# TXn_v1_2.net
KiCad netlist of a schematic drawn in EAGLE
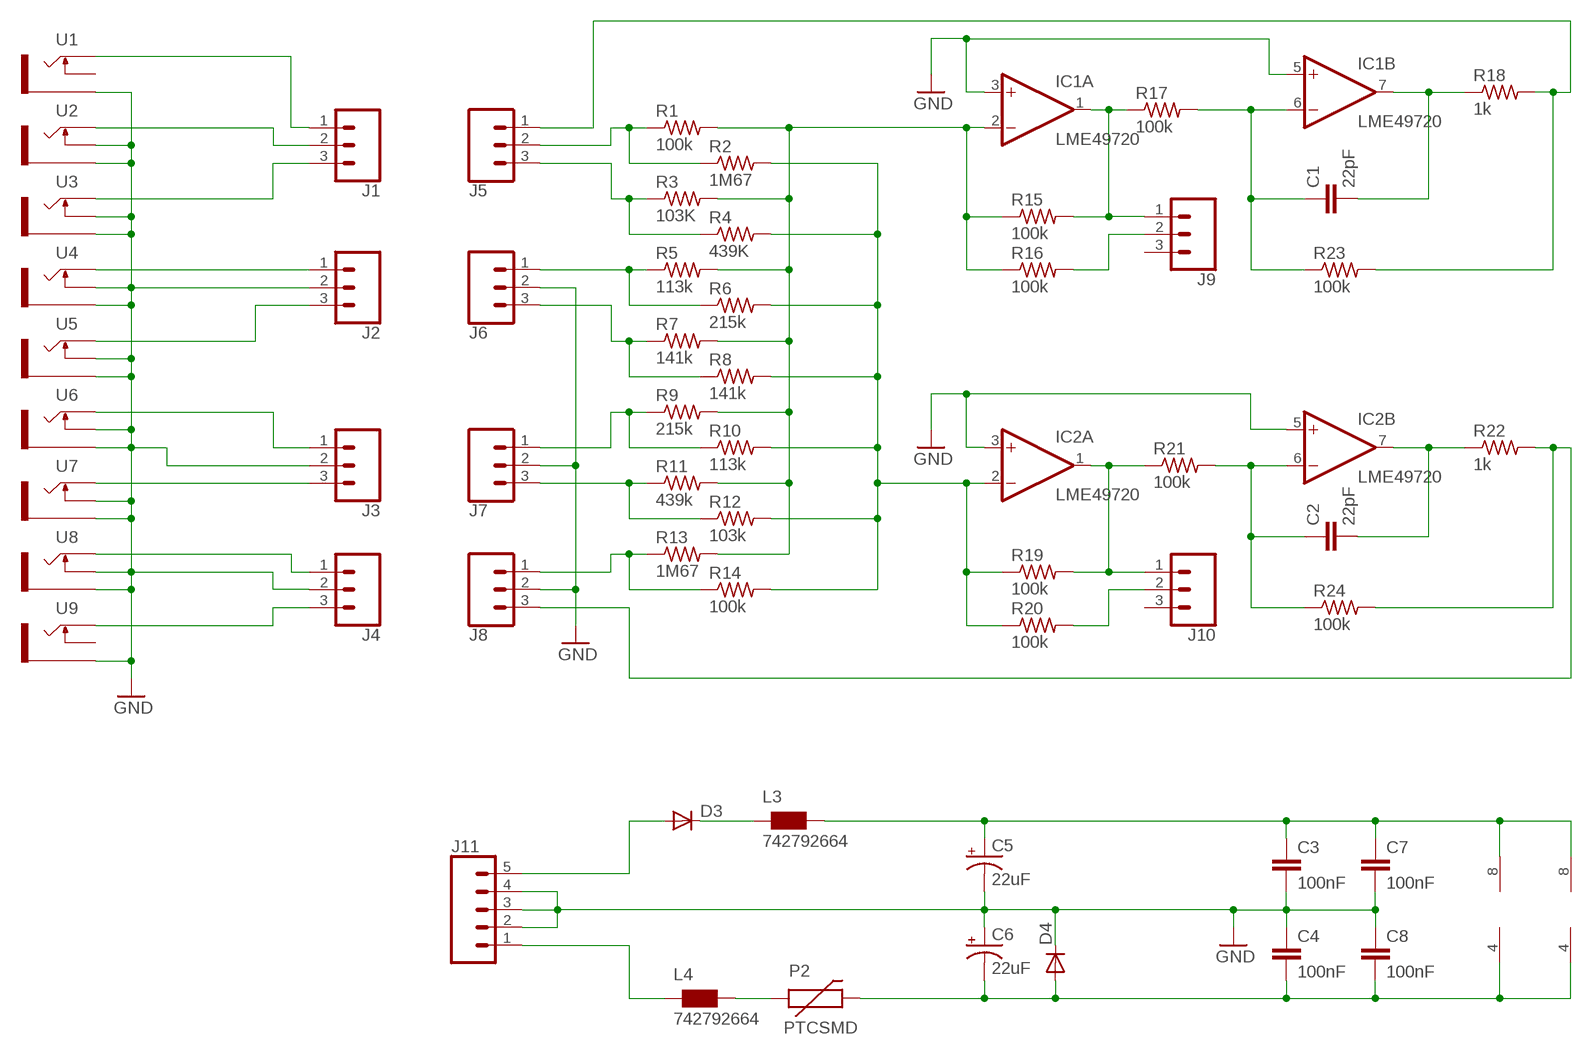
[diagram p0: schematic, sheet 1]

(export (version "E")
  (design (tool "Eeschema 10.0.6"))
  (components
    (comp (ref "C1")
      (value "22pF")
      (footprint "eagle-import:0603-CAP")
      (libsource (lib "eagle-import") (part "CAP0603-CAP"))
    )
    (comp (ref "C2")
      (value "22pF")
      (footprint "eagle-import:0603-CAP")
      (libsource (lib "eagle-import") (part "CAP0603-CAP"))
    )
    (comp (ref "C3")
      (value "100nF")
      (footprint "eagle-import:0603-CAP")
      (libsource (lib "eagle-import") (part "CAP0603-CAP"))
    )
    (comp (ref "C4")
      (value "100nF")
      (footprint "eagle-import:0603-CAP")
      (libsource (lib "eagle-import") (part "CAP0603-CAP"))
    )
    (comp (ref "C5")
      (value "22uF")
      (footprint "eagle-import:PANASONIC_B")
      (libsource (lib "eagle-import") (part "CPOL-USB"))
    )
    (comp (ref "C6")
      (value "22uF")
      (footprint "eagle-import:PANASONIC_B")
      (libsource (lib "eagle-import") (part "CPOL-USB"))
    )
    (comp (ref "C7")
      (value "100nF")
      (footprint "eagle-import:0603-CAP")
      (libsource (lib "eagle-import") (part "CAP0603-CAP"))
    )
    (comp (ref "C8")
      (value "100nF")
      (footprint "eagle-import:0603-CAP")
      (libsource (lib "eagle-import") (part "CAP0603-CAP"))
    )
    (comp (ref "D3")
      (value "DIODE-SOD123")
      (footprint "eagle-import:SOD123")
      (libsource (lib "eagle-import") (part "DIODE-SOD123"))
    )
    (comp (ref "D4")
      (value "DIODE-SOD123")
      (footprint "eagle-import:SOD123")
      (libsource (lib "eagle-import") (part "DIODE-SOD123"))
    )
    (comp (ref "IC1")
      (value "LME49720")
      (footprint "eagle-import:SO08")
      (fields (field (name "SPICEPREFIX") "J"))
      (libsource (lib "eagle-import") (part "TL072D"))
    )
    (comp (ref "IC2")
      (value "LME49720")
      (footprint "eagle-import:SO08")
      (libsource (lib "eagle-import") (part "TL072D"))
    )
    (comp (ref "J1")
      (value "CONN_031X03_NO_SILK")
      (footprint "eagle-import:1X03_NO_SILK")
      (libsource (lib "eagle-import") (part "CONN_031X03_NO_SILK"))
    )
    (comp (ref "J2")
      (value "CONN_031X03_NO_SILK")
      (footprint "eagle-import:1X03_NO_SILK")
      (libsource (lib "eagle-import") (part "CONN_031X03_NO_SILK"))
    )
    (comp (ref "J3")
      (value "CONN_031X03_NO_SILK")
      (footprint "eagle-import:1X03_NO_SILK")
      (libsource (lib "eagle-import") (part "CONN_031X03_NO_SILK"))
    )
    (comp (ref "J4")
      (value "CONN_031X03_NO_SILK")
      (footprint "eagle-import:1X03_NO_SILK")
      (libsource (lib "eagle-import") (part "CONN_031X03_NO_SILK"))
    )
    (comp (ref "J5")
      (value "CONN_031X03_NO_SILK")
      (footprint "eagle-import:1X03_NO_SILK")
      (libsource (lib "eagle-import") (part "CONN_031X03_NO_SILK"))
    )
    (comp (ref "J6")
      (value "CONN_031X03_NO_SILK")
      (footprint "eagle-import:1X03_NO_SILK")
      (libsource (lib "eagle-import") (part "CONN_031X03_NO_SILK"))
    )
    (comp (ref "J7")
      (value "CONN_031X03_NO_SILK")
      (footprint "eagle-import:1X03_NO_SILK")
      (libsource (lib "eagle-import") (part "CONN_031X03_NO_SILK"))
    )
    (comp (ref "J8")
      (value "CONN_031X03_NO_SILK")
      (footprint "eagle-import:1X03_NO_SILK")
      (libsource (lib "eagle-import") (part "CONN_031X03_NO_SILK"))
    )
    (comp (ref "J9")
      (value "CONN_031X03_NO_SILK")
      (footprint "eagle-import:1X03_NO_SILK")
      (libsource (lib "eagle-import") (part "CONN_031X03_NO_SILK"))
    )
    (comp (ref "J10")
      (value "CONN_031X03_NO_SILK")
      (footprint "eagle-import:1X03_NO_SILK")
      (libsource (lib "eagle-import") (part "CONN_031X03_NO_SILK"))
    )
    (comp (ref "J11")
      (value "CONN_05NO_SILK")
      (footprint "eagle-import:1X05_NO_SILK")
      (libsource (lib "eagle-import") (part "CONN_05NO_SILK"))
    )
    (comp (ref "L3")
      (value "742792664")
      (footprint "eagle-import:0603")
      (libsource (lib "eagle-import") (part "WE-CBF_0603"))
    )
    (comp (ref "L4")
      (value "742792664")
      (footprint "eagle-import:0603")
      (libsource (lib "eagle-import") (part "WE-CBF_0603"))
    )
    (comp (ref "P2")
      (value "PTCSMD")
      (footprint "eagle-import:PTC-1206")
      (libsource (lib "eagle-import") (part "PTCSMD"))
    )
    (comp (ref "R1")
      (value "100k")
      (footprint "eagle-import:R0603")
      (libsource (lib "eagle-import") (part "R-US_R0603"))
    )
    (comp (ref "R2")
      (value "1M67")
      (footprint "eagle-import:R0603")
      (libsource (lib "eagle-import") (part "R-US_R0603"))
    )
    (comp (ref "R3")
      (value "103K")
      (footprint "eagle-import:R0603")
      (libsource (lib "eagle-import") (part "R-US_R0603"))
    )
    (comp (ref "R4")
      (value "439K")
      (footprint "eagle-import:R0603")
      (libsource (lib "eagle-import") (part "R-US_R0603"))
    )
    (comp (ref "R5")
      (value "113k")
      (footprint "eagle-import:R0603")
      (libsource (lib "eagle-import") (part "R-US_R0603"))
    )
    (comp (ref "R6")
      (value "215k")
      (footprint "eagle-import:R0603")
      (libsource (lib "eagle-import") (part "R-US_R0603"))
    )
    (comp (ref "R7")
      (value "141k")
      (footprint "eagle-import:R0603")
      (libsource (lib "eagle-import") (part "R-US_R0603"))
    )
    (comp (ref "R8")
      (value "141k")
      (footprint "eagle-import:R0603")
      (libsource (lib "eagle-import") (part "R-US_R0603"))
    )
    (comp (ref "R9")
      (value "215k")
      (footprint "eagle-import:R0603")
      (libsource (lib "eagle-import") (part "R-US_R0603"))
    )
    (comp (ref "R10")
      (value "113k")
      (footprint "eagle-import:R0603")
      (libsource (lib "eagle-import") (part "R-US_R0603"))
    )
    (comp (ref "R11")
      (value "439k")
      (footprint "eagle-import:R0603")
      (libsource (lib "eagle-import") (part "R-US_R0603"))
    )
    (comp (ref "R12")
      (value "103k")
      (footprint "eagle-import:R0603")
      (libsource (lib "eagle-import") (part "R-US_R0603"))
    )
    (comp (ref "R13")
      (value "1M67")
      (footprint "eagle-import:R0603")
      (libsource (lib "eagle-import") (part "R-US_R0603"))
    )
    (comp (ref "R14")
      (value "100k")
      (footprint "eagle-import:R0603")
      (libsource (lib "eagle-import") (part "R-US_R0603"))
    )
    (comp (ref "R15")
      (value "100k")
      (footprint "eagle-import:R0603")
      (libsource (lib "eagle-import") (part "R-US_R0603"))
    )
    (comp (ref "R16")
      (value "100k")
      (footprint "eagle-import:R0603")
      (libsource (lib "eagle-import") (part "R-US_R0603"))
    )
    (comp (ref "R17")
      (value "100k")
      (footprint "eagle-import:R0603")
      (libsource (lib "eagle-import") (part "R-US_R0603"))
    )
    (comp (ref "R18")
      (value "1k")
      (footprint "eagle-import:R0603")
      (libsource (lib "eagle-import") (part "R-US_R0603"))
    )
    (comp (ref "R19")
      (value "100k")
      (footprint "eagle-import:R0603")
      (libsource (lib "eagle-import") (part "R-US_R0603"))
    )
    (comp (ref "R20")
      (value "100k")
      (footprint "eagle-import:R0603")
      (libsource (lib "eagle-import") (part "R-US_R0603"))
    )
    (comp (ref "R21")
      (value "100k")
      (footprint "eagle-import:R0603")
      (libsource (lib "eagle-import") (part "R-US_R0603"))
    )
    (comp (ref "R22")
      (value "1k")
      (footprint "eagle-import:R0603")
      (libsource (lib "eagle-import") (part "R-US_R0603"))
    )
    (comp (ref "R23")
      (value "100k")
      (footprint "eagle-import:R0603")
      (libsource (lib "eagle-import") (part "R-US_R0603"))
    )
    (comp (ref "R24")
      (value "100k")
      (footprint "eagle-import:R0603")
      (libsource (lib "eagle-import") (part "R-US_R0603"))
    )
    (comp (ref "U1")
      (value "THONKICONNLEFT")
      (footprint "eagle-import:WQP-PJ301M-12_JACK_L")
      (libsource (lib "eagle-import") (part "THONKICONNLEFT"))
    )
    (comp (ref "U2")
      (value "THONKICONNLEFT")
      (footprint "eagle-import:WQP-PJ301M-12_JACK_L")
      (libsource (lib "eagle-import") (part "THONKICONNLEFT"))
    )
    (comp (ref "U3")
      (value "THONKICONNLEFT")
      (footprint "eagle-import:WQP-PJ301M-12_JACK_L")
      (libsource (lib "eagle-import") (part "THONKICONNLEFT"))
    )
    (comp (ref "U4")
      (value "THONKICONNLEFT")
      (footprint "eagle-import:WQP-PJ301M-12_JACK_L")
      (libsource (lib "eagle-import") (part "THONKICONNLEFT"))
    )
    (comp (ref "U5")
      (value "THONKICONNLEFT")
      (footprint "eagle-import:WQP-PJ301M-12_JACK_L")
      (libsource (lib "eagle-import") (part "THONKICONNLEFT"))
    )
    (comp (ref "U6")
      (value "THONKICONNLEFT")
      (footprint "eagle-import:WQP-PJ301M-12_JACK_L")
      (libsource (lib "eagle-import") (part "THONKICONNLEFT"))
    )
    (comp (ref "U7")
      (value "THONKICONNLEFT")
      (footprint "eagle-import:WQP-PJ301M-12_JACK_L")
      (libsource (lib "eagle-import") (part "THONKICONNLEFT"))
    )
    (comp (ref "U8")
      (value "THONKICONNLEFT")
      (footprint "eagle-import:WQP-PJ301M-12_JACK_L")
      (libsource (lib "eagle-import") (part "THONKICONNLEFT"))
    )
    (comp (ref "U9")
      (value "THONKICONNLEFT")
      (footprint "eagle-import:WQP-PJ301M-12_JACK_L")
      (libsource (lib "eagle-import") (part "THONKICONNLEFT"))
    )
  )
  (nets
    (net (code "1") (name "GND") (class "Default")
      (node (ref "C3") (pin "2") (pinfunction "2_2") (pintype "passive"))
      (node (ref "C4") (pin "1") (pinfunction "1_1") (pintype "passive"))
      (node (ref "C5") (pin "-") (pinfunction "-_-") (pintype "passive"))
      (node (ref "C6") (pin "+") (pinfunction "+_+") (pintype "passive"))
      (node (ref "C7") (pin "2") (pinfunction "2_2") (pintype "passive"))
      (node (ref "C8") (pin "1") (pinfunction "1_1") (pintype "passive"))
      (node (ref "D4") (pin "C") (pinfunction "C_C") (pintype "passive"))
      (node (ref "IC1") (pin "3") (pinfunction "+IN_3") (pintype "input"))
      (node (ref "IC1") (pin "5") (pinfunction "+IN_5") (pintype "input"))
      (node (ref "IC2") (pin "3") (pinfunction "+IN_3") (pintype "input"))
      (node (ref "IC2") (pin "5") (pinfunction "+IN_5") (pintype "input"))
      (node (ref "J11") (pin "2") (pinfunction "2_2") (pintype "passive"))
      (node (ref "J11") (pin "3") (pinfunction "3_3") (pintype "passive"))
      (node (ref "J11") (pin "4") (pinfunction "4_4") (pintype "passive"))
      (node (ref "J2") (pin "2") (pinfunction "2_2") (pintype "passive"))
      (node (ref "J3") (pin "2") (pinfunction "2_2") (pintype "passive"))
      (node (ref "J4") (pin "2") (pinfunction "2_2") (pintype "passive"))
      (node (ref "J6") (pin "2") (pinfunction "2_2") (pintype "passive"))
      (node (ref "J7") (pin "2") (pinfunction "2_2") (pintype "passive"))
      (node (ref "J8") (pin "2") (pinfunction "2_2") (pintype "passive"))
      (node (ref "U1") (pin "P$3_SLEEVE") (pinfunction "SLEEVE_P$3_SLEEVE") (pintype "passive"))
      (node (ref "U2") (pin "P$2_SWITCH") (pinfunction "SWITCH_P$2_SWITCH") (pintype "passive"))
      (node (ref "U2") (pin "P$3_SLEEVE") (pinfunction "SLEEVE_P$3_SLEEVE") (pintype "passive"))
      (node (ref "U3") (pin "P$2_SWITCH") (pinfunction "SWITCH_P$2_SWITCH") (pintype "passive"))
      (node (ref "U3") (pin "P$3_SLEEVE") (pinfunction "SLEEVE_P$3_SLEEVE") (pintype "passive"))
      (node (ref "U4") (pin "P$2_SWITCH") (pinfunction "SWITCH_P$2_SWITCH") (pintype "passive"))
      (node (ref "U4") (pin "P$3_SLEEVE") (pinfunction "SLEEVE_P$3_SLEEVE") (pintype "passive"))
      (node (ref "U5") (pin "P$2_SWITCH") (pinfunction "SWITCH_P$2_SWITCH") (pintype "passive"))
      (node (ref "U5") (pin "P$3_SLEEVE") (pinfunction "SLEEVE_P$3_SLEEVE") (pintype "passive"))
      (node (ref "U6") (pin "P$2_SWITCH") (pinfunction "SWITCH_P$2_SWITCH") (pintype "passive"))
      (node (ref "U6") (pin "P$3_SLEEVE") (pinfunction "SLEEVE_P$3_SLEEVE") (pintype "passive"))
      (node (ref "U7") (pin "P$2_SWITCH") (pinfunction "SWITCH_P$2_SWITCH") (pintype "passive"))
      (node (ref "U7") (pin "P$3_SLEEVE") (pinfunction "SLEEVE_P$3_SLEEVE") (pintype "passive"))
      (node (ref "U8") (pin "P$2_SWITCH") (pinfunction "SWITCH_P$2_SWITCH") (pintype "passive"))
      (node (ref "U8") (pin "P$3_SLEEVE") (pinfunction "SLEEVE_P$3_SLEEVE") (pintype "passive"))
      (node (ref "U9") (pin "P$3_SLEEVE") (pinfunction "SLEEVE_P$3_SLEEVE") (pintype "passive"))
    )
    (net (code "2") (name "Net-(D3-PadA)") (class "Default")
      (node (ref "D3") (pin "A") (pinfunction "A_A") (pintype "passive"))
      (node (ref "J11") (pin "5") (pinfunction "5_5") (pintype "passive"))
    )
    (net (code "3") (name "Net-(D3-PadC)") (class "Default")
      (node (ref "D3") (pin "C") (pinfunction "C_C") (pintype "passive"))
      (node (ref "L3") (pin "1") (pinfunction "1_1") (pintype "passive"))
    )
    (net (code "4") (name "Net-(IC1A--IN)") (class "Default")
      (node (ref "IC1") (pin "2") (pinfunction "-IN_2") (pintype "input"))
      (node (ref "R1") (pin "2") (pinfunction "2_2") (pintype "passive"))
      (node (ref "R11") (pin "2") (pinfunction "2_2") (pintype "passive"))
      (node (ref "R13") (pin "2") (pinfunction "2_2") (pintype "passive"))
      (node (ref "R15") (pin "1") (pinfunction "1_1") (pintype "passive"))
      (node (ref "R16") (pin "1") (pinfunction "1_1") (pintype "passive"))
      (node (ref "R3") (pin "2") (pinfunction "2_2") (pintype "passive"))
      (node (ref "R5") (pin "2") (pinfunction "2_2") (pintype "passive"))
      (node (ref "R7") (pin "2") (pinfunction "2_2") (pintype "passive"))
      (node (ref "R9") (pin "2") (pinfunction "2_2") (pintype "passive"))
    )
    (net (code "5") (name "Net-(IC1A-OUT)") (class "Default")
      (node (ref "IC1") (pin "1") (pinfunction "OUT_1") (pintype "output"))
      (node (ref "J9") (pin "1") (pinfunction "1_1") (pintype "passive"))
      (node (ref "R15") (pin "2") (pinfunction "2_2") (pintype "passive"))
      (node (ref "R17") (pin "1") (pinfunction "1_1") (pintype "passive"))
    )
    (net (code "6") (name "Net-(IC1B--IN)") (class "Default")
      (node (ref "C1") (pin "1") (pinfunction "1_1") (pintype "passive"))
      (node (ref "IC1") (pin "6") (pinfunction "-IN_6") (pintype "input"))
      (node (ref "R17") (pin "2") (pinfunction "2_2") (pintype "passive"))
      (node (ref "R23") (pin "1") (pinfunction "1_1") (pintype "passive"))
    )
    (net (code "7") (name "Net-(IC1B-OUT)") (class "Default")
      (node (ref "C1") (pin "2") (pinfunction "2_2") (pintype "passive"))
      (node (ref "IC1") (pin "7") (pinfunction "OUT_7") (pintype "output"))
      (node (ref "R18") (pin "1") (pinfunction "1_1") (pintype "passive"))
    )
    (net (code "8") (name "Net-(IC1C-V+)") (class "Default")
      (node (ref "C3") (pin "1") (pinfunction "1_1") (pintype "passive"))
      (node (ref "C5") (pin "+") (pinfunction "+_+") (pintype "passive"))
      (node (ref "C7") (pin "1") (pinfunction "1_1") (pintype "passive"))
      (node (ref "IC1") (pin "8") (pinfunction "V+_8") (pintype "power_in"))
      (node (ref "IC2") (pin "8") (pinfunction "V+_8") (pintype "power_in"))
      (node (ref "L3") (pin "2") (pinfunction "2_2") (pintype "passive"))
    )
    (net (code "9") (name "Net-(IC1C-V-)") (class "Default")
      (node (ref "C4") (pin "2") (pinfunction "2_2") (pintype "passive"))
      (node (ref "C6") (pin "-") (pinfunction "-_-") (pintype "passive"))
      (node (ref "C8") (pin "2") (pinfunction "2_2") (pintype "passive"))
      (node (ref "D4") (pin "A") (pinfunction "A_A") (pintype "passive"))
      (node (ref "IC1") (pin "4") (pinfunction "V-_4") (pintype "power_in"))
      (node (ref "IC2") (pin "4") (pinfunction "V-_4") (pintype "power_in"))
      (node (ref "P2") (pin "2") (pinfunction "2_2") (pintype "bidirectional"))
    )
    (net (code "10") (name "Net-(IC2A--IN)") (class "Default")
      (node (ref "IC2") (pin "2") (pinfunction "-IN_2") (pintype "input"))
      (node (ref "R10") (pin "2") (pinfunction "2_2") (pintype "passive"))
      (node (ref "R12") (pin "2") (pinfunction "2_2") (pintype "passive"))
      (node (ref "R14") (pin "2") (pinfunction "2_2") (pintype "passive"))
      (node (ref "R19") (pin "1") (pinfunction "1_1") (pintype "passive"))
      (node (ref "R2") (pin "2") (pinfunction "2_2") (pintype "passive"))
      (node (ref "R20") (pin "1") (pinfunction "1_1") (pintype "passive"))
      (node (ref "R4") (pin "2") (pinfunction "2_2") (pintype "passive"))
      (node (ref "R6") (pin "2") (pinfunction "2_2") (pintype "passive"))
      (node (ref "R8") (pin "2") (pinfunction "2_2") (pintype "passive"))
    )
    (net (code "11") (name "Net-(IC2A-OUT)") (class "Default")
      (node (ref "IC2") (pin "1") (pinfunction "OUT_1") (pintype "output"))
      (node (ref "J10") (pin "1") (pinfunction "1_1") (pintype "passive"))
      (node (ref "R19") (pin "2") (pinfunction "2_2") (pintype "passive"))
      (node (ref "R21") (pin "1") (pinfunction "1_1") (pintype "passive"))
    )
    (net (code "12") (name "Net-(IC2B--IN)") (class "Default")
      (node (ref "C2") (pin "1") (pinfunction "1_1") (pintype "passive"))
      (node (ref "IC2") (pin "6") (pinfunction "-IN_6") (pintype "input"))
      (node (ref "R21") (pin "2") (pinfunction "2_2") (pintype "passive"))
      (node (ref "R24") (pin "1") (pinfunction "1_1") (pintype "passive"))
    )
    (net (code "13") (name "Net-(IC2B-OUT)") (class "Default")
      (node (ref "C2") (pin "2") (pinfunction "2_2") (pintype "passive"))
      (node (ref "IC2") (pin "7") (pinfunction "OUT_7") (pintype "output"))
      (node (ref "R22") (pin "1") (pinfunction "1_1") (pintype "passive"))
    )
    (net (code "14") (name "Net-(J5-Pad1)") (class "Default")
      (node (ref "J5") (pin "1") (pinfunction "1_1") (pintype "passive"))
      (node (ref "R18") (pin "2") (pinfunction "2_2") (pintype "passive"))
      (node (ref "R23") (pin "2") (pinfunction "2_2") (pintype "passive"))
    )
    (net (code "15") (name "Net-(J5-Pad2)") (class "Default")
      (node (ref "J5") (pin "2") (pinfunction "2_2") (pintype "passive"))
      (node (ref "R1") (pin "1") (pinfunction "1_1") (pintype "passive"))
      (node (ref "R2") (pin "1") (pinfunction "1_1") (pintype "passive"))
    )
    (net (code "16") (name "Net-(J5-Pad3)") (class "Default")
      (node (ref "J5") (pin "3") (pinfunction "3_3") (pintype "passive"))
      (node (ref "R3") (pin "1") (pinfunction "1_1") (pintype "passive"))
      (node (ref "R4") (pin "1") (pinfunction "1_1") (pintype "passive"))
    )
    (net (code "17") (name "Net-(J6-Pad1)") (class "Default")
      (node (ref "J6") (pin "1") (pinfunction "1_1") (pintype "passive"))
      (node (ref "R5") (pin "1") (pinfunction "1_1") (pintype "passive"))
      (node (ref "R6") (pin "1") (pinfunction "1_1") (pintype "passive"))
    )
    (net (code "18") (name "Net-(J6-Pad3)") (class "Default")
      (node (ref "J6") (pin "3") (pinfunction "3_3") (pintype "passive"))
      (node (ref "R7") (pin "1") (pinfunction "1_1") (pintype "passive"))
      (node (ref "R8") (pin "1") (pinfunction "1_1") (pintype "passive"))
    )
    (net (code "19") (name "Net-(J7-Pad1)") (class "Default")
      (node (ref "J7") (pin "1") (pinfunction "1_1") (pintype "passive"))
      (node (ref "R10") (pin "1") (pinfunction "1_1") (pintype "passive"))
      (node (ref "R9") (pin "1") (pinfunction "1_1") (pintype "passive"))
    )
    (net (code "20") (name "Net-(J7-Pad3)") (class "Default")
      (node (ref "J7") (pin "3") (pinfunction "3_3") (pintype "passive"))
      (node (ref "R11") (pin "1") (pinfunction "1_1") (pintype "passive"))
      (node (ref "R12") (pin "1") (pinfunction "1_1") (pintype "passive"))
    )
    (net (code "21") (name "Net-(J8-Pad1)") (class "Default")
      (node (ref "J8") (pin "1") (pinfunction "1_1") (pintype "passive"))
      (node (ref "R13") (pin "1") (pinfunction "1_1") (pintype "passive"))
      (node (ref "R14") (pin "1") (pinfunction "1_1") (pintype "passive"))
    )
    (net (code "22") (name "Net-(J8-Pad3)") (class "Default")
      (node (ref "J8") (pin "3") (pinfunction "3_3") (pintype "passive"))
      (node (ref "R22") (pin "2") (pinfunction "2_2") (pintype "passive"))
      (node (ref "R24") (pin "2") (pinfunction "2_2") (pintype "passive"))
    )
    (net (code "23") (name "Net-(J9-Pad2)") (class "Default")
      (node (ref "J9") (pin "2") (pinfunction "2_2") (pintype "passive"))
      (node (ref "R16") (pin "2") (pinfunction "2_2") (pintype "passive"))
    )
    (net (code "24") (name "Net-(J10-Pad2)") (class "Default")
      (node (ref "J10") (pin "2") (pinfunction "2_2") (pintype "passive"))
      (node (ref "R20") (pin "2") (pinfunction "2_2") (pintype "passive"))
    )
    (net (code "25") (name "Net-(J11-Pad1)") (class "Default")
      (node (ref "J11") (pin "1") (pinfunction "1_1") (pintype "passive"))
      (node (ref "L4") (pin "1") (pinfunction "1_1") (pintype "passive"))
    )
    (net (code "26") (name "Net-(L4-Pad2)") (class "Default")
      (node (ref "L4") (pin "2") (pinfunction "2_2") (pintype "passive"))
      (node (ref "P2") (pin "1") (pinfunction "1_1") (pintype "bidirectional"))
    )
    (net (code "27") (name "Net-(U1-TIP)") (class "Default")
      (node (ref "J1") (pin "1") (pinfunction "1_1") (pintype "passive"))
      (node (ref "U1") (pin "P$1_TIP") (pinfunction "TIP_P$1_TIP") (pintype "passive"))
    )
    (net (code "28") (name "Net-(U2-TIP)") (class "Default")
      (node (ref "J1") (pin "2") (pinfunction "2_2") (pintype "passive"))
      (node (ref "U2") (pin "P$1_TIP") (pinfunction "TIP_P$1_TIP") (pintype "passive"))
    )
    (net (code "29") (name "Net-(U3-TIP)") (class "Default")
      (node (ref "J1") (pin "3") (pinfunction "3_3") (pintype "passive"))
      (node (ref "U3") (pin "P$1_TIP") (pinfunction "TIP_P$1_TIP") (pintype "passive"))
    )
    (net (code "30") (name "Net-(U4-TIP)") (class "Default")
      (node (ref "J2") (pin "1") (pinfunction "1_1") (pintype "passive"))
      (node (ref "U4") (pin "P$1_TIP") (pinfunction "TIP_P$1_TIP") (pintype "passive"))
    )
    (net (code "31") (name "Net-(U5-TIP)") (class "Default")
      (node (ref "J2") (pin "3") (pinfunction "3_3") (pintype "passive"))
      (node (ref "U5") (pin "P$1_TIP") (pinfunction "TIP_P$1_TIP") (pintype "passive"))
    )
    (net (code "32") (name "Net-(U6-TIP)") (class "Default")
      (node (ref "J3") (pin "1") (pinfunction "1_1") (pintype "passive"))
      (node (ref "U6") (pin "P$1_TIP") (pinfunction "TIP_P$1_TIP") (pintype "passive"))
    )
    (net (code "33") (name "Net-(U7-TIP)") (class "Default")
      (node (ref "J3") (pin "3") (pinfunction "3_3") (pintype "passive"))
      (node (ref "U7") (pin "P$1_TIP") (pinfunction "TIP_P$1_TIP") (pintype "passive"))
    )
    (net (code "34") (name "Net-(U8-TIP)") (class "Default")
      (node (ref "J4") (pin "1") (pinfunction "1_1") (pintype "passive"))
      (node (ref "U8") (pin "P$1_TIP") (pinfunction "TIP_P$1_TIP") (pintype "passive"))
    )
    (net (code "35") (name "Net-(U9-TIP)") (class "Default")
      (node (ref "J4") (pin "3") (pinfunction "3_3") (pintype "passive"))
      (node (ref "U9") (pin "P$1_TIP") (pinfunction "TIP_P$1_TIP") (pintype "passive"))
    )
    (net (code "36") (name "unconnected-(J9-Pad3)") (class "Default")
      (node (ref "J9") (pin "3") (pinfunction "3_3") (pintype "passive"))
    )
    (net (code "37") (name "unconnected-(J10-Pad3)") (class "Default")
      (node (ref "J10") (pin "3") (pinfunction "3_3") (pintype "passive"))
    )
    (net (code "38") (name "unconnected-(U1-SWITCH-PadP$2_SWITCH)") (class "Default")
      (node (ref "U1") (pin "P$2_SWITCH") (pinfunction "SWITCH_P$2_SWITCH") (pintype "passive"))
    )
    (net (code "39") (name "unconnected-(U9-SWITCH-PadP$2_SWITCH)") (class "Default")
      (node (ref "U9") (pin "P$2_SWITCH") (pinfunction "SWITCH_P$2_SWITCH") (pintype "passive"))
    )
  )
)
